# 06_INERTIAL_SENSOR.net
KiCad netlist of a schematic drawn in Altium Designer
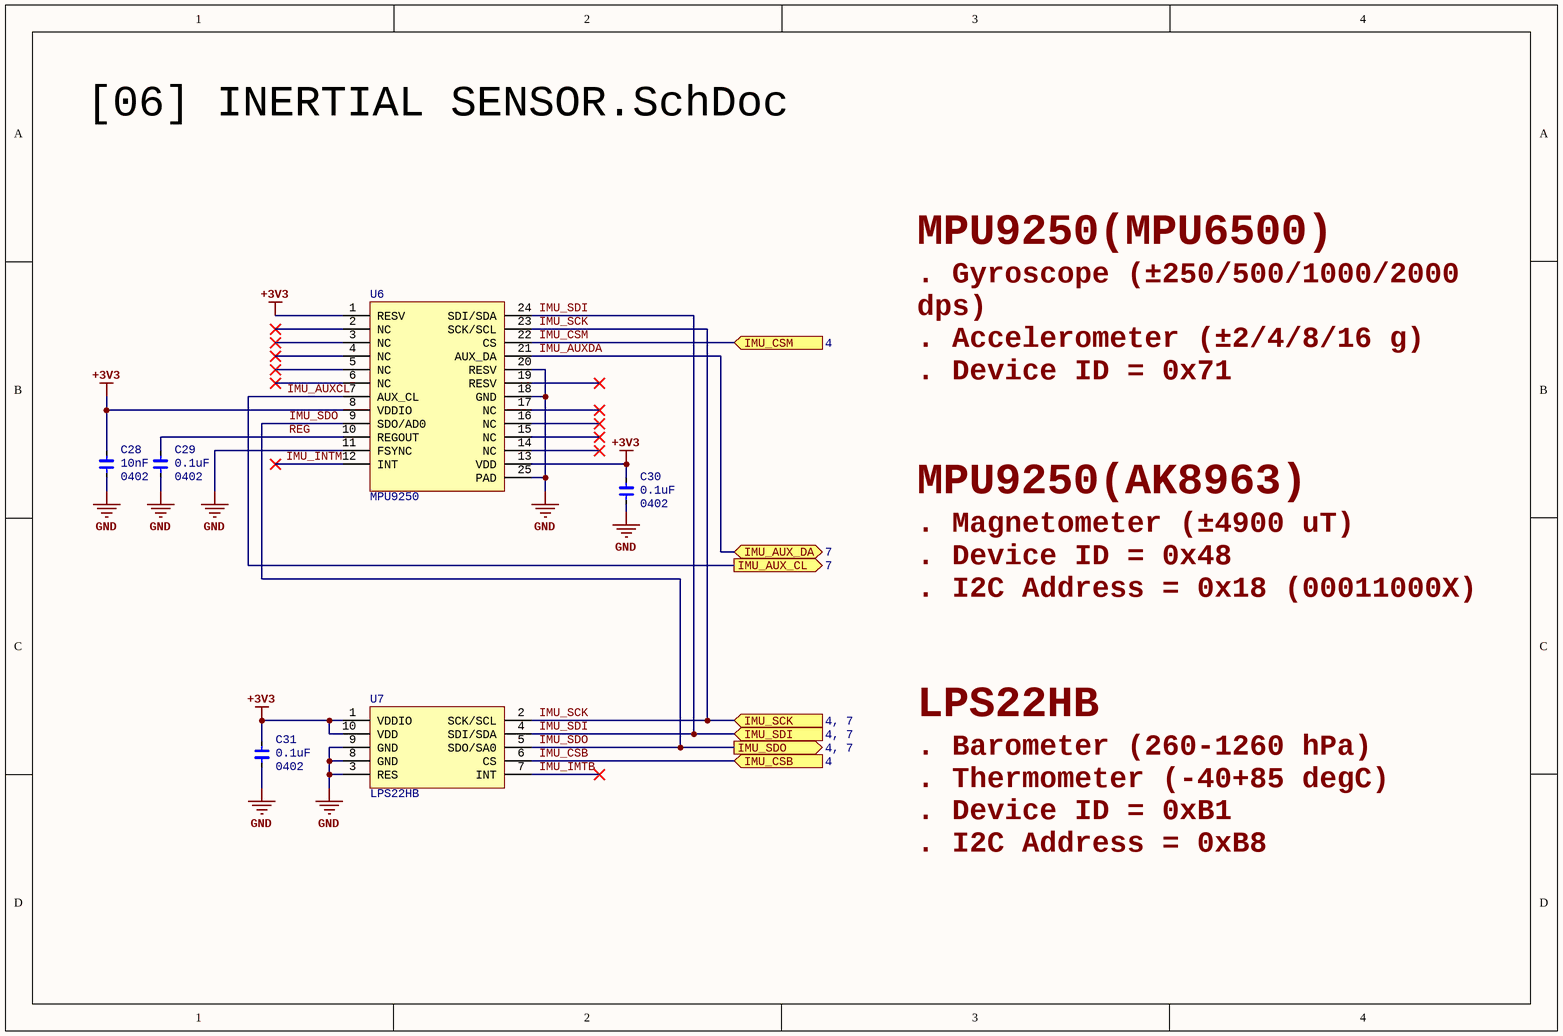
[diagram p0: [06] INERTIAL SENSOR.SchDoc]

(export (version "E")
  (design (tool "Eeschema 10.0.6"))
  (components
    (comp (ref "C28")
      (value "10nF")
      (footprint "PCB_PassiveCap:CAP_0402")
      (description "Capacitor")
      (fields (field (name "TYPE") "0402") (field (name "Comment") "C0402"))
      (libsource (lib "SCH_Passive") (part "Cap_0402"))
    )
    (comp (ref "C29")
      (value "0.1uF")
      (footprint "PCB_PassiveCap:CAP_0402")
      (description "Capacitor")
      (fields (field (name "TYPE") "0402") (field (name "Comment") "C0402"))
      (libsource (lib "SCH_Passive") (part "Cap_0402"))
    )
    (comp (ref "C30")
      (value "0.1uF")
      (footprint "PCB_PassiveCap:CAP_0402")
      (description "Capacitor")
      (fields (field (name "TYPE") "0402") (field (name "Comment") "C0402"))
      (libsource (lib "SCH_Passive") (part "Cap_0402"))
    )
    (comp (ref "C31")
      (value "0.1uF")
      (footprint "PCB_PassiveCap:CAP_0402")
      (description "Capacitor")
      (fields (field (name "TYPE") "0402") (field (name "Comment") "C0402"))
      (libsource (lib "SCH_Passive") (part "Cap_0402"))
    )
    (comp (ref "U6")
      (value "MPU9250")
      (footprint "PCB_IntegratedCircuit:QFN_P0.4_24")
      (description "Sensor Motion")
      (libsource (lib "SCH_IntegratedCircuit") (part "MPU925x"))
    )
    (comp (ref "U7")
      (value "LPS22HB")
      (footprint "PCB_IntegratedCircuit:HCLGA-2x2_10")
      (description "Sensor Pressure")
      (libsource (lib "SCH_IntegratedCircuit") (part "LPS22HB"))
    )
  )
  (nets
    (net (code "1") (name "+3V3") (class "Default")
      (node (ref "C28") (pin "2") (pinfunction "2_2") (pintype "passive"))
      (node (ref "C30") (pin "2") (pinfunction "2_2") (pintype "passive"))
      (node (ref "C31") (pin "2") (pinfunction "2_2") (pintype "passive"))
      (node (ref "U6") (pin "1") (pinfunction "RESV_1") (pintype "passive"))
      (node (ref "U6") (pin "13") (pinfunction "VDD_13") (pintype "passive"))
      (node (ref "U6") (pin "8") (pinfunction "VDDIO_8") (pintype "passive"))
      (node (ref "U7") (pin "1") (pinfunction "VDDIO_1") (pintype "passive"))
      (node (ref "U7") (pin "10") (pinfunction "VDD_10") (pintype "passive"))
    )
    (net (code "2") (name "/IMU_AUXCL") (class "Default")
      (node (ref "U6") (pin "7") (pinfunction "AUX_CL_7") (pintype "passive"))
    )
    (net (code "3") (name "/IMU_AUXDA") (class "Default")
      (node (ref "U6") (pin "21") (pinfunction "AUX_DA_21") (pintype "passive"))
    )
    (net (code "4") (name "/IMU_CSB") (class "Default")
      (node (ref "U7") (pin "6") (pinfunction "CS_6") (pintype "passive"))
    )
    (net (code "5") (name "/IMU_CSM") (class "Default")
      (node (ref "U6") (pin "22") (pinfunction "CS_22") (pintype "passive"))
    )
    (net (code "6") (name "/IMU_IMTB") (class "Default")
      (node (ref "U7") (pin "7") (pinfunction "INT_7") (pintype "passive+no_connect"))
    )
    (net (code "7") (name "/IMU_INTM") (class "Default")
      (node (ref "U6") (pin "12") (pinfunction "INT_12") (pintype "passive+no_connect"))
    )
    (net (code "8") (name "/IMU_SCK") (class "Default")
      (node (ref "U6") (pin "23") (pinfunction "SCK/SCL_23") (pintype "passive"))
      (node (ref "U7") (pin "2") (pinfunction "SCK/SCL_2") (pintype "passive"))
    )
    (net (code "9") (name "/IMU_SDI") (class "Default")
      (node (ref "U6") (pin "24") (pinfunction "SDI/SDA_24") (pintype "passive"))
      (node (ref "U7") (pin "4") (pinfunction "SDI/SDA_4") (pintype "passive"))
    )
    (net (code "10") (name "/IMU_SDO") (class "Default")
      (node (ref "U6") (pin "9") (pinfunction "SDO/AD0_9") (pintype "passive"))
      (node (ref "U7") (pin "5") (pinfunction "SDO/SA0_5") (pintype "passive"))
    )
    (net (code "11") (name "/REG") (class "Default")
      (node (ref "C29") (pin "2") (pinfunction "2_2") (pintype "passive"))
      (node (ref "U6") (pin "10") (pinfunction "REGOUT_10") (pintype "passive"))
    )
    (net (code "12") (name "GND") (class "Default")
      (node (ref "C28") (pin "1") (pinfunction "1_1") (pintype "passive"))
      (node (ref "C29") (pin "1") (pinfunction "1_1") (pintype "passive"))
      (node (ref "C30") (pin "1") (pinfunction "1_1") (pintype "passive"))
      (node (ref "C31") (pin "1") (pinfunction "1_1") (pintype "passive"))
      (node (ref "U6") (pin "11") (pinfunction "FSYNC_11") (pintype "passive"))
      (node (ref "U6") (pin "18") (pinfunction "GND_18") (pintype "passive"))
      (node (ref "U6") (pin "20") (pinfunction "RESV_20") (pintype "passive"))
      (node (ref "U6") (pin "25") (pinfunction "PAD_25") (pintype "passive"))
      (node (ref "U7") (pin "3") (pinfunction "RES_3") (pintype "passive"))
      (node (ref "U7") (pin "8") (pinfunction "GND_8") (pintype "passive"))
      (node (ref "U7") (pin "9") (pinfunction "GND_9") (pintype "passive"))
    )
    (net (code "13") (name "unconnected-(U6-NC-Pad2)") (class "Default")
      (node (ref "U6") (pin "2") (pinfunction "NC_2") (pintype "passive+no_connect"))
    )
    (net (code "14") (name "unconnected-(U6-NC-Pad3)") (class "Default")
      (node (ref "U6") (pin "3") (pinfunction "NC_3") (pintype "passive+no_connect"))
    )
    (net (code "15") (name "unconnected-(U6-NC-Pad4)") (class "Default")
      (node (ref "U6") (pin "4") (pinfunction "NC_4") (pintype "passive+no_connect"))
    )
    (net (code "16") (name "unconnected-(U6-NC-Pad5)") (class "Default")
      (node (ref "U6") (pin "5") (pinfunction "NC_5") (pintype "passive+no_connect"))
    )
    (net (code "17") (name "unconnected-(U6-NC-Pad6)") (class "Default")
      (node (ref "U6") (pin "6") (pinfunction "NC_6") (pintype "passive+no_connect"))
    )
    (net (code "18") (name "unconnected-(U6-NC-Pad14)") (class "Default")
      (node (ref "U6") (pin "14") (pinfunction "NC_14") (pintype "passive+no_connect"))
    )
    (net (code "19") (name "unconnected-(U6-NC-Pad15)") (class "Default")
      (node (ref "U6") (pin "15") (pinfunction "NC_15") (pintype "passive+no_connect"))
    )
    (net (code "20") (name "unconnected-(U6-NC-Pad16)") (class "Default")
      (node (ref "U6") (pin "16") (pinfunction "NC_16") (pintype "passive+no_connect"))
    )
    (net (code "21") (name "unconnected-(U6-NC-Pad17)") (class "Default")
      (node (ref "U6") (pin "17") (pinfunction "NC_17") (pintype "passive+no_connect"))
    )
    (net (code "22") (name "unconnected-(U6-RESV-Pad19)") (class "Default")
      (node (ref "U6") (pin "19") (pinfunction "RESV_19") (pintype "passive+no_connect"))
    )
  )
)
